# Motor_2.net
KiCad netlist of a schematic drawn in Altium Designer
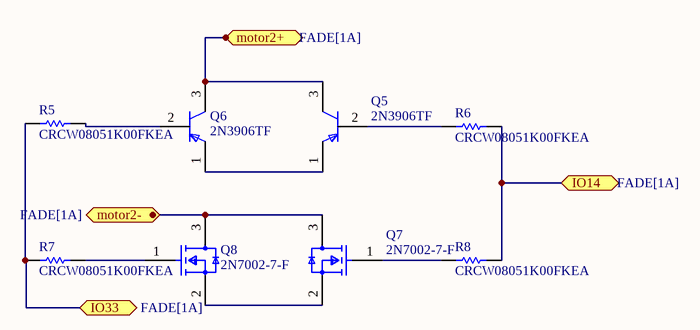
[diagram p0: Motor_2.SchDoc]

(export (version "E")
  (design (tool "Eeschema 10.0.6"))
  (components
    (comp (ref "Q5")
      (value "2N3906TF")
      (footprint "FP-135AR-MFG")
      (description "2N3906TF Small Signal Bipolar Transistor, 0.2A I(C), 40V V(BR)CEO, 1-Element, PNP, Silicon, TO-92")
      (libsource (lib "Altium Content Vault") (part "40d2b7e180a7bcff784209620afba3e"))
    )
    (comp (ref "Q6")
      (value "2N3906TF")
      (footprint "FP-135AR-MFG")
      (description "2N3906TF Small Signal Bipolar Transistor, 0.2A I(C), 40V V(BR)CEO, 1-Element, PNP, Silicon, TO-92")
      (libsource (lib "Altium Content Vault") (part "40d2b7e180a7bcff784209620afba3e"))
    )
    (comp (ref "Q7")
      (value "2N7002-7-F")
      (footprint "FP-SOT23-MFG")
      (description "MOSFET N-CH 60V 115MA SOT23-3")
      (fields (field (name "VOLTAGE") "60V"))
      (libsource (lib "Altium Content Vault") (part "3b9c635fedb024a5347a57b145af9cc"))
    )
    (comp (ref "Q8")
      (value "2N7002-7-F")
      (footprint "FP-SOT23-MFG")
      (description "MOSFET N-CH 60V 115MA SOT23-3")
      (fields (field (name "VOLTAGE") "60V"))
      (libsource (lib "Altium Content Vault") (part "3b9c635fedb024a5347a57b145af9cc"))
    )
    (comp (ref "R5")
      (value "CRCW08051K00FKEA")
      (footprint "RESC2013X50X30NL20T20")
      (fields (field (name "MANUFACTURER") "Vishay Dale"))
      (libsource (lib "Altium Content Vault") (part "RES"))
    )
    (comp (ref "R6")
      (value "CRCW08051K00FKEA")
      (footprint "RESC2013X50X30NL20T20")
      (fields (field (name "MANUFACTURER") "Vishay Dale"))
      (libsource (lib "Altium Content Vault") (part "RES"))
    )
    (comp (ref "R7")
      (value "CRCW08051K00FKEA")
      (footprint "RESC2013X50X30NL20T20")
      (fields (field (name "MANUFACTURER") "Vishay Dale"))
      (libsource (lib "Altium Content Vault") (part "RES"))
    )
    (comp (ref "R8")
      (value "CRCW08051K00FKEA")
      (footprint "RESC2013X50X30NL20T20")
      (fields (field (name "MANUFACTURER") "Vishay Dale"))
      (libsource (lib "Altium Content Vault") (part "RES"))
    )
  )
  (nets
    (net (code "1") (name "/IO14") (class "Default")
      (node (ref "R6") (pin "2") (pinfunction "2_2") (pintype "passive"))
      (node (ref "R8") (pin "2") (pinfunction "2_2") (pintype "passive"))
    )
    (net (code "2") (name "/IO33") (class "Default")
      (node (ref "R5") (pin "1") (pinfunction "1_1") (pintype "passive"))
      (node (ref "R7") (pin "1") (pinfunction "1_1") (pintype "passive"))
    )
    (net (code "3") (name "/motor2+") (class "Default")
      (node (ref "Q5") (pin "3") (pinfunction "C_3") (pintype "passive"))
      (node (ref "Q6") (pin "3") (pinfunction "C_3") (pintype "passive"))
    )
    (net (code "4") (name "/motor2-") (class "Default")
      (node (ref "Q7") (pin "3") (pinfunction "D_3") (pintype "passive"))
      (node (ref "Q8") (pin "3") (pinfunction "D_3") (pintype "passive"))
    )
    (net (code "5") (name "Net-(Q5-B)") (class "Default")
      (node (ref "Q5") (pin "2") (pinfunction "B_2") (pintype "passive"))
      (node (ref "R6") (pin "1") (pinfunction "1_1") (pintype "passive"))
    )
    (net (code "6") (name "Net-(Q5-E)") (class "Default")
      (node (ref "Q5") (pin "1") (pinfunction "E_1") (pintype "passive"))
      (node (ref "Q6") (pin "1") (pinfunction "E_1") (pintype "passive"))
    )
    (net (code "7") (name "Net-(Q6-B)") (class "Default")
      (node (ref "Q6") (pin "2") (pinfunction "B_2") (pintype "passive"))
      (node (ref "R5") (pin "2") (pinfunction "2_2") (pintype "passive"))
    )
    (net (code "8") (name "Net-(Q7-G)") (class "Default")
      (node (ref "Q7") (pin "1") (pinfunction "G_1") (pintype "passive"))
      (node (ref "R8") (pin "1") (pinfunction "1_1") (pintype "passive"))
    )
    (net (code "9") (name "Net-(Q7-S)") (class "Default")
      (node (ref "Q7") (pin "2") (pinfunction "S_2") (pintype "passive"))
      (node (ref "Q8") (pin "2") (pinfunction "S_2") (pintype "passive"))
    )
    (net (code "10") (name "Net-(Q8-G)") (class "Default")
      (node (ref "Q8") (pin "1") (pinfunction "G_1") (pintype "passive"))
      (node (ref "R7") (pin "2") (pinfunction "2_2") (pintype "passive"))
    )
  )
)
